# ST-Link-V2_2.net
KiCad netlist of a schematic drawn in Altium Designer
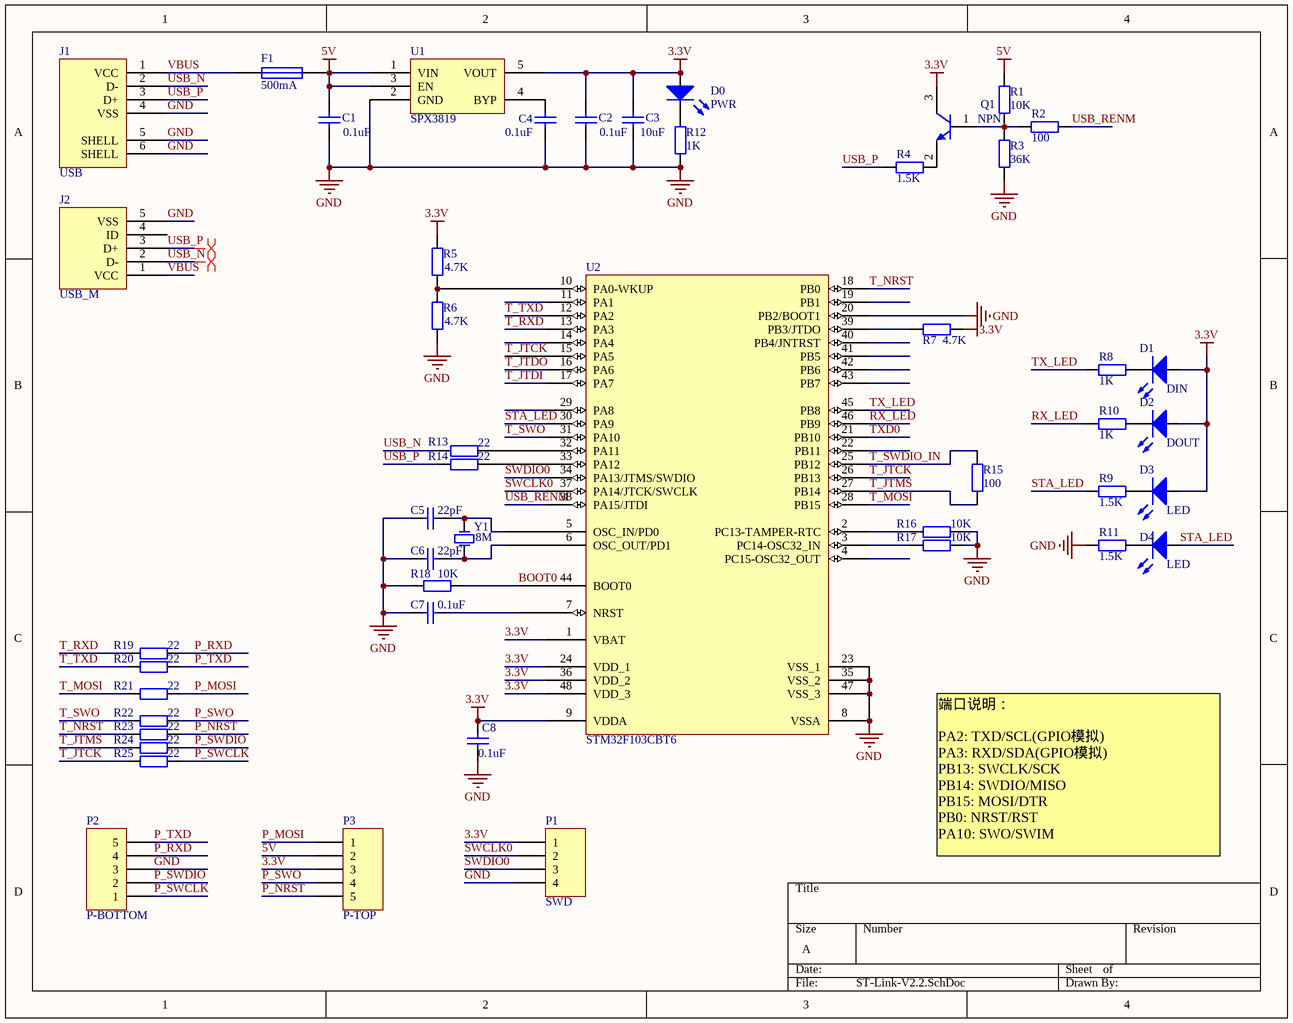
[diagram p0: ST-Link-V2.2.SchDoc]

(export (version "E")
  (design (tool "Eeschema 10.0.6"))
  (components
    (comp (ref "C1")
      (value "0.1uF")
      (footprint "C-0603")
      (description "Capacitor")
      (fields (field (name "Comment") "Cap") (field (name "PUBLISHER") "Altium Limited"))
      (libsource (lib "Miscellaneous Devices") (part "Cap"))
    )
    (comp (ref "C2")
      (value "0.1uF")
      (footprint "C-0603")
      (description "Capacitor")
      (fields (field (name "Comment") "Cap") (field (name "PUBLISHER") "Altium Limited"))
      (libsource (lib "Miscellaneous Devices") (part "Cap"))
    )
    (comp (ref "C3")
      (value "10uF")
      (footprint "C-0603")
      (description "Capacitor")
      (fields (field (name "Comment") "Cap") (field (name "PUBLISHER") "Altium Limited"))
      (libsource (lib "Miscellaneous Devices") (part "Cap"))
    )
    (comp (ref "C4")
      (value "0.1uF")
      (footprint "C-0603")
      (description "Capacitor")
      (fields (field (name "Comment") "Cap") (field (name "PUBLISHER") "Altium Limited"))
      (libsource (lib "Miscellaneous Devices") (part "Cap"))
    )
    (comp (ref "C5")
      (value "22pF")
      (footprint "C-0603")
      (fields (field (name "Comment") "Cap"))
      (libsource (lib "WK_PCB") (part "Cap"))
    )
    (comp (ref "C6")
      (value "22pF")
      (footprint "C-0603")
      (fields (field (name "Comment") "Cap"))
      (libsource (lib "WK_PCB") (part "Cap"))
    )
    (comp (ref "C7")
      (value "0.1uF")
      (footprint "C-0603")
      (fields (field (name "Comment") "Cap"))
      (libsource (lib "WK_PCB") (part "Cap"))
    )
    (comp (ref "C8")
      (value "0.1uF")
      (footprint "C-0603")
      (description "Capacitor")
      (fields (field (name "Comment") "Cap") (field (name "PUBLISHER") "Altium Limited"))
      (libsource (lib "Miscellaneous Devices") (part "Cap"))
    )
    (comp (ref "D0")
      (value "PWR")
      (footprint "SMT_LED_0603")
      (description "Typical RED, GREEN, YELLOW, AMBER GaAs LED")
      (fields (field (name "PUBLISHER") "Altium Limited"))
      (libsource (lib "ST-Link-V2.2") (part "LED2"))
    )
    (comp (ref "D1")
      (value "DIN")
      (footprint "SMT_LED_0603")
      (description "Typical RED, GREEN, YELLOW, AMBER GaAs LED")
      (fields (field (name "PUBLISHER") "Altium Limited"))
      (libsource (lib "ST-Link-V2.2") (part "LED2"))
    )
    (comp (ref "D2")
      (value "DOUT")
      (footprint "SMT_LED_0603")
      (description "Typical RED, GREEN, YELLOW, AMBER GaAs LED")
      (fields (field (name "PUBLISHER") "Altium Limited"))
      (libsource (lib "ST-Link-V2.2") (part "LED2"))
    )
    (comp (ref "D3")
      (value "LED")
      (footprint "SMT_LED_0603")
      (description "Typical RED, GREEN, YELLOW, AMBER GaAs LED")
      (fields (field (name "PUBLISHER") "Altium Limited"))
      (libsource (lib "ST-Link-V2.2") (part "LED2"))
    )
    (comp (ref "D4")
      (value "LED")
      (footprint "SMT_LED_0603")
      (description "Typical RED, GREEN, YELLOW, AMBER GaAs LED")
      (fields (field (name "PUBLISHER") "Altium Limited"))
      (libsource (lib "ST-Link-V2.2") (part "LED2"))
    )
    (comp (ref "F1")
      (value "500mA")
      (footprint "0805-1")
      (description "保险丝")
      (fields (field (name "Comment") "Fuse1"))
      (libsource (lib "ST-Link-V2.2") (part "Fuse1"))
    )
    (comp (ref "J1")
      (value "USB")
      (footprint "USB-B")
      (description "USB接口")
      (libsource (lib "HDR_Fszhang") (part "USB"))
    )
    (comp (ref "J2")
      (value "USB_M")
      (footprint "USB_MICRO_5S_B")
      (description "Micro/Mini USB")
      (libsource (lib "HDR_Fszhang") (part "USB_M"))
    )
    (comp (ref "P1")
      (value "SWD")
      (footprint "SIP4-1.27")
      (description "Header, 4-Pin")
      (fields (field (name "PUBLISHER") "Altium Limited"))
      (libsource (lib "Miscellaneous Connectors") (part "Header 4"))
    )
    (comp (ref "P2")
      (value "P-BOTTOM")
      (footprint "HEADER_5")
      (description "Header, 5-Pin")
      (fields (field (name "PUBLISHER") "Altium Limited"))
      (libsource (lib "") (part "Header 5_1"))
    )
    (comp (ref "P3")
      (value "P-TOP")
      (footprint "HEADER_5")
      (description "Header, 5-Pin")
      (fields (field (name "PUBLISHER") "Altium Limited"))
      (libsource (lib "Miscellaneous Connectors") (part "Header 5"))
    )
    (comp (ref "Q1")
      (value "NPN")
      (footprint "SOT23-3")
      (description "贴片三极管")
      (fields (field (name "PUBLISHER") "Altium Limited"))
      (libsource (lib "Fszhang") (part "NPN1"))
    )
    (comp (ref "R1")
      (value "10K")
      (footprint "0603-1")
      (description "贴片电阻")
      (fields (field (name "Comment") "Res1") (field (name "PUBLISHER") "Altium Limited"))
      (libsource (lib "Fszhang") (part "Res1"))
    )
    (comp (ref "R2")
      (value "100")
      (footprint "0603-1")
      (description "贴片电阻")
      (fields (field (name "Comment") "Res1") (field (name "PUBLISHER") "Altium Limited"))
      (libsource (lib "") (part "Res1_1"))
    )
    (comp (ref "R3")
      (value "36K")
      (footprint "0603-1")
      (description "贴片电阻")
      (fields (field (name "Comment") "Res1") (field (name "PUBLISHER") "Altium Limited"))
      (libsource (lib "Fszhang") (part "Res1"))
    )
    (comp (ref "R4")
      (value "1.5K")
      (footprint "0603-1")
      (description "贴片电阻")
      (fields (field (name "Comment") "Res1") (field (name "PUBLISHER") "Altium Limited"))
      (libsource (lib "") (part "Res1_2"))
    )
    (comp (ref "R5")
      (value "4.7K")
      (footprint "0603-1")
      (description "Resistor")
      (fields (field (name "Comment") "Res2") (field (name "PUBLISHER") "Altium Limited"))
      (libsource (lib "") (part "Res2_1"))
    )
    (comp (ref "R6")
      (value "4.7K")
      (footprint "0603-1")
      (description "Resistor")
      (fields (field (name "Comment") "Res2") (field (name "PUBLISHER") "Altium Limited"))
      (libsource (lib "") (part "Res2_1"))
    )
    (comp (ref "R7")
      (value "4.7K")
      (footprint "0603-1")
      (description "Resistor")
      (fields (field (name "Comment") "Res2") (field (name "PUBLISHER") "Altium Limited"))
      (libsource (lib "Miscellaneous Devices") (part "Res2"))
    )
    (comp (ref "R8")
      (value "1K")
      (footprint "0603-1")
      (description "Resistor")
      (fields (field (name "Comment") "Res2") (field (name "PUBLISHER") "Altium Limited"))
      (libsource (lib "Miscellaneous Devices") (part "Res2"))
    )
    (comp (ref "R9")
      (value "1.5K")
      (footprint "0603-1")
      (description "Resistor")
      (fields (field (name "Comment") "Res2") (field (name "PUBLISHER") "Altium Limited"))
      (libsource (lib "") (part "Res2_2"))
    )
    (comp (ref "R10")
      (value "1K")
      (footprint "0603-1")
      (description "Resistor")
      (fields (field (name "Comment") "Res2") (field (name "PUBLISHER") "Altium Limited"))
      (libsource (lib "Miscellaneous Devices") (part "Res2"))
    )
    (comp (ref "R11")
      (value "1.5K")
      (footprint "0603-1")
      (description "Resistor")
      (fields (field (name "Comment") "Res2") (field (name "PUBLISHER") "Altium Limited"))
      (libsource (lib "") (part "Res2_1"))
    )
    (comp (ref "R12")
      (value "1K")
      (footprint "0603-1")
      (description "Resistor")
      (fields (field (name "Comment") "Res2") (field (name "PUBLISHER") "Altium Limited"))
      (libsource (lib "") (part "Res2_1"))
    )
    (comp (ref "R13")
      (value "22")
      (footprint "0603-1")
      (description "Resistor")
      (fields (field (name "Comment") "Res2") (field (name "PUBLISHER") "Altium Limited"))
      (libsource (lib "Miscellaneous Devices") (part "Res2"))
    )
    (comp (ref "R14")
      (value "22")
      (footprint "0603-1")
      (description "Resistor")
      (fields (field (name "Comment") "Res2") (field (name "PUBLISHER") "Altium Limited"))
      (libsource (lib "Miscellaneous Devices") (part "Res2"))
    )
    (comp (ref "R15")
      (value "100")
      (footprint "0603-1")
      (description "Resistor")
      (fields (field (name "Comment") "Res2") (field (name "PUBLISHER") "Altium Limited"))
      (libsource (lib "") (part "Res2_1"))
    )
    (comp (ref "R16")
      (value "10K")
      (footprint "0603-1")
      (description "贴片电阻")
      (fields (field (name "Comment") "Res1") (field (name "PUBLISHER") "Altium Limited"))
      (libsource (lib "") (part "Res1_1"))
    )
    (comp (ref "R17")
      (value "10K")
      (footprint "0603-1")
      (description "贴片电阻")
      (fields (field (name "Comment") "Res1") (field (name "PUBLISHER") "Altium Limited"))
      (libsource (lib "") (part "Res1_1"))
    )
    (comp (ref "R18")
      (value "10K")
      (footprint "0603-1")
      (description "Resistor")
      (fields (field (name "Comment") "Res2") (field (name "PUBLISHER") "Altium Limited"))
      (libsource (lib "Miscellaneous Devices") (part "Res2"))
    )
    (comp (ref "R19")
      (value "22")
      (footprint "0603-1")
      (description "Resistor")
      (fields (field (name "Comment") "Res2") (field (name "PUBLISHER") "Altium Limited"))
      (libsource (lib "Miscellaneous Devices") (part "Res2"))
    )
    (comp (ref "R20")
      (value "22")
      (footprint "0603-1")
      (description "Resistor")
      (fields (field (name "Comment") "Res2") (field (name "PUBLISHER") "Altium Limited"))
      (libsource (lib "Miscellaneous Devices") (part "Res2"))
    )
    (comp (ref "R21")
      (value "22")
      (footprint "0603-1")
      (description "Resistor")
      (fields (field (name "Comment") "Res2") (field (name "PUBLISHER") "Altium Limited"))
      (libsource (lib "Miscellaneous Devices") (part "Res2"))
    )
    (comp (ref "R22")
      (value "22")
      (footprint "0603-1")
      (description "Resistor")
      (fields (field (name "Comment") "Res2") (field (name "PUBLISHER") "Altium Limited"))
      (libsource (lib "Miscellaneous Devices") (part "Res2"))
    )
    (comp (ref "R23")
      (value "22")
      (footprint "0603-1")
      (description "Resistor")
      (fields (field (name "Comment") "Res2") (field (name "PUBLISHER") "Altium Limited"))
      (libsource (lib "Miscellaneous Devices") (part "Res2"))
    )
    (comp (ref "R24")
      (value "22")
      (footprint "0603-1")
      (description "Resistor")
      (fields (field (name "Comment") "Res2") (field (name "PUBLISHER") "Altium Limited"))
      (libsource (lib "Miscellaneous Devices") (part "Res2"))
    )
    (comp (ref "R25")
      (value "22")
      (footprint "0603-1")
      (description "Resistor")
      (fields (field (name "Comment") "Res2") (field (name "PUBLISHER") "Altium Limited"))
      (libsource (lib "Miscellaneous Devices") (part "Res2"))
    )
    (comp (ref "U1") (value "SPX3819") (footprint "SOT23-5") (libsource (lib "Schlib1") (part "SPX3819")))
    (comp (ref "U2")
      (value "STM32F103CBT6")
      (footprint "LQFP48_N")
      (description "STM32 ARM-based 32-bit MCU with 64 Kbytes Flash, 48-pin LQFP, Industrial Temperature")
      (fields (field (name "PUBLISHER") "Altium Limited"))
      (libsource (lib "ST Microcontroller 32-Bit STM32") (part "STM32F103C8T6"))
    )
    (comp (ref "Y1")
      (value "8M")
      (footprint "XAL5032 2-Leads")
      (description "Crystal Oscillator")
      (fields
        (field (name "MANUFACTURER") "Generic Components")
        (field (name "PUBLISHER") "Altium Hobart Technology Centre")
      )
      (libsource (lib "*") (part "XTAL"))
    )
  )
  (nets
    (net (code "1") (name "/BOOT0") (class "Default")
      (node (ref "R18") (pin "2") (pinfunction "2_2") (pintype "passive"))
      (node (ref "U2") (pin "44") (pinfunction "BOOT0_44") (pintype "passive"))
    )
    (net (code "2") (name "/P_MOSI") (class "Default")
      (node (ref "P3") (pin "1") (pinfunction "1_1") (pintype "passive"))
      (node (ref "R21") (pin "2") (pinfunction "2_2") (pintype "passive"))
    )
    (net (code "3") (name "/P_NRST") (class "Default")
      (node (ref "P3") (pin "5") (pinfunction "5_5") (pintype "passive"))
      (node (ref "R23") (pin "2") (pinfunction "2_2") (pintype "passive"))
    )
    (net (code "4") (name "/P_RXD") (class "Default")
      (node (ref "P2") (pin "4") (pinfunction "4_4") (pintype "passive"))
      (node (ref "R19") (pin "2") (pinfunction "2_2") (pintype "passive"))
    )
    (net (code "5") (name "/P_SWCLK") (class "Default")
      (node (ref "P2") (pin "1") (pinfunction "1_1") (pintype "passive"))
      (node (ref "R25") (pin "2") (pinfunction "2_2") (pintype "passive"))
    )
    (net (code "6") (name "/P_SWDIO") (class "Default")
      (node (ref "P2") (pin "2") (pinfunction "2_2") (pintype "passive"))
      (node (ref "R24") (pin "2") (pinfunction "2_2") (pintype "passive"))
    )
    (net (code "7") (name "/P_SWO") (class "Default")
      (node (ref "P3") (pin "4") (pinfunction "4_4") (pintype "passive"))
      (node (ref "R22") (pin "2") (pinfunction "2_2") (pintype "passive"))
    )
    (net (code "8") (name "/P_TXD") (class "Default")
      (node (ref "P2") (pin "5") (pinfunction "5_5") (pintype "passive"))
      (node (ref "R20") (pin "2") (pinfunction "2_2") (pintype "passive"))
    )
    (net (code "9") (name "/RX_LED") (class "Default")
      (node (ref "R10") (pin "1") (pinfunction "1_1") (pintype "passive"))
      (node (ref "U2") (pin "46") (pinfunction "PB9_46") (pintype "bidirectional"))
    )
    (net (code "10") (name "/STA_LED") (class "Default")
      (node (ref "D4") (pin "1") (pinfunction "A_1") (pintype "passive"))
      (node (ref "R9") (pin "2") (pinfunction "2_2") (pintype "passive"))
      (node (ref "U2") (pin "30") (pinfunction "PA9_30") (pintype "bidirectional"))
    )
    (net (code "11") (name "/SWCLK0") (class "Default")
      (node (ref "P1") (pin "2") (pinfunction "2_2") (pintype "passive"))
      (node (ref "U2") (pin "37") (pinfunction "PA14/JTCK/SWCLK_37") (pintype "bidirectional"))
    )
    (net (code "12") (name "/SWDIO0") (class "Default")
      (node (ref "P1") (pin "3") (pinfunction "3_3") (pintype "passive"))
      (node (ref "U2") (pin "34") (pinfunction "PA13/JTMS/SWDIO_34") (pintype "bidirectional"))
    )
    (net (code "13") (name "/TXD0") (class "Default")
      (node (ref "U2") (pin "21") (pinfunction "PB10_21") (pintype "bidirectional"))
    )
    (net (code "14") (name "/TX_LED") (class "Default")
      (node (ref "R8") (pin "1") (pinfunction "1_1") (pintype "passive"))
      (node (ref "U2") (pin "45") (pinfunction "PB8_45") (pintype "bidirectional"))
    )
    (net (code "15") (name "/T_JTCK") (class "Default")
      (node (ref "R25") (pin "1") (pinfunction "1_1") (pintype "passive"))
      (node (ref "U2") (pin "15") (pinfunction "PA5_15") (pintype "bidirectional"))
      (node (ref "U2") (pin "26") (pinfunction "PB13_26") (pintype "bidirectional"))
    )
    (net (code "16") (name "/T_JTDI") (class "Default")
      (node (ref "U2") (pin "17") (pinfunction "PA7_17") (pintype "bidirectional"))
    )
    (net (code "17") (name "/T_JTDO") (class "Default")
      (node (ref "U2") (pin "16") (pinfunction "PA6_16") (pintype "bidirectional"))
    )
    (net (code "18") (name "/T_JTMS") (class "Default")
      (node (ref "R15") (pin "1") (pinfunction "1_1") (pintype "passive"))
      (node (ref "R24") (pin "1") (pinfunction "1_1") (pintype "passive"))
      (node (ref "U2") (pin "27") (pinfunction "PB14_27") (pintype "bidirectional"))
    )
    (net (code "19") (name "/T_MOSI") (class "Default")
      (node (ref "R21") (pin "1") (pinfunction "1_1") (pintype "passive"))
      (node (ref "U2") (pin "28") (pinfunction "PB15_28") (pintype "bidirectional"))
    )
    (net (code "20") (name "/T_NRST") (class "Default")
      (node (ref "R23") (pin "1") (pinfunction "1_1") (pintype "passive"))
      (node (ref "U2") (pin "18") (pinfunction "PB0_18") (pintype "bidirectional"))
    )
    (net (code "21") (name "/T_RXD") (class "Default")
      (node (ref "R19") (pin "1") (pinfunction "1_1") (pintype "passive"))
      (node (ref "U2") (pin "13") (pinfunction "PA3_13") (pintype "bidirectional"))
    )
    (net (code "22") (name "/T_SWDIO_IN") (class "Default")
      (node (ref "R15") (pin "2") (pinfunction "2_2") (pintype "passive"))
      (node (ref "U2") (pin "25") (pinfunction "PB12_25") (pintype "bidirectional"))
    )
    (net (code "23") (name "/T_SWO") (class "Default")
      (node (ref "R22") (pin "1") (pinfunction "1_1") (pintype "passive"))
      (node (ref "U2") (pin "31") (pinfunction "PA10_31") (pintype "bidirectional"))
    )
    (net (code "24") (name "/T_TXD") (class "Default")
      (node (ref "R20") (pin "1") (pinfunction "1_1") (pintype "passive"))
      (node (ref "U2") (pin "12") (pinfunction "PA2_12") (pintype "bidirectional"))
    )
    (net (code "25") (name "/USB_N") (class "Default")
      (node (ref "J1") (pin "2") (pinfunction "D-_2") (pintype "passive"))
      (node (ref "J2") (pin "2") (pinfunction "D-_2") (pintype "passive"))
      (node (ref "R13") (pin "1") (pinfunction "1_1") (pintype "passive"))
    )
    (net (code "26") (name "/USB_P") (class "Default")
      (node (ref "J1") (pin "3") (pinfunction "D+_3") (pintype "passive"))
      (node (ref "J2") (pin "3") (pinfunction "D+_3") (pintype "passive"))
      (node (ref "R14") (pin "1") (pinfunction "1_1") (pintype "passive"))
      (node (ref "R4") (pin "2") (pinfunction "2_2") (pintype "passive"))
    )
    (net (code "27") (name "/USB_RENM") (class "Default")
      (node (ref "R2") (pin "2") (pinfunction "2_2") (pintype "passive"))
      (node (ref "U2") (pin "38") (pinfunction "PA15/JTDI_38") (pintype "bidirectional"))
    )
    (net (code "28") (name "/VBUS") (class "Default")
      (node (ref "F1") (pin "1") (pinfunction "1_1") (pintype "passive"))
      (node (ref "J1") (pin "1") (pinfunction "VCC_1") (pintype "passive"))
      (node (ref "J2") (pin "1") (pinfunction "VCC_1") (pintype "passive"))
    )
    (net (code "29") (name "3.3V") (class "Default")
      (node (ref "C2") (pin "2") (pinfunction "2_2") (pintype "passive"))
      (node (ref "C3") (pin "2") (pinfunction "2_2") (pintype "passive"))
      (node (ref "C8") (pin "2") (pinfunction "2_2") (pintype "passive"))
      (node (ref "D0") (pin "1") (pinfunction "A_1") (pintype "passive"))
      (node (ref "D1") (pin "1") (pinfunction "A_1") (pintype "passive"))
      (node (ref "D2") (pin "1") (pinfunction "A_1") (pintype "passive"))
      (node (ref "D3") (pin "1") (pinfunction "A_1") (pintype "passive"))
      (node (ref "P1") (pin "1") (pinfunction "1_1") (pintype "passive"))
      (node (ref "P3") (pin "3") (pinfunction "3_3") (pintype "passive"))
      (node (ref "Q1") (pin "3") (pinfunction "C_3") (pintype "passive"))
      (node (ref "R5") (pin "2") (pinfunction "2_2") (pintype "passive"))
      (node (ref "R7") (pin "2") (pinfunction "2_2") (pintype "passive"))
      (node (ref "U1") (pin "5") (pinfunction "VOUT_5") (pintype "passive"))
      (node (ref "U2") (pin "1") (pinfunction "VBAT_1") (pintype "power_in"))
      (node (ref "U2") (pin "24") (pinfunction "VDD_1_24") (pintype "power_in"))
      (node (ref "U2") (pin "36") (pinfunction "VDD_2_36") (pintype "power_in"))
      (node (ref "U2") (pin "48") (pinfunction "VDD_3_48") (pintype "power_in"))
      (node (ref "U2") (pin "9") (pinfunction "VDDA_9") (pintype "power_in"))
    )
    (net (code "30") (name "5V") (class "Default")
      (node (ref "C1") (pin "2") (pinfunction "2_2") (pintype "passive"))
      (node (ref "F1") (pin "2") (pinfunction "2_2") (pintype "passive"))
      (node (ref "P3") (pin "2") (pinfunction "2_2") (pintype "passive"))
      (node (ref "R1") (pin "1") (pinfunction "1_1") (pintype "passive"))
      (node (ref "U1") (pin "1") (pinfunction "VIN_1") (pintype "passive"))
      (node (ref "U1") (pin "3") (pinfunction "EN_3") (pintype "passive"))
    )
    (net (code "31") (name "GND") (class "Default")
      (node (ref "C1") (pin "1") (pinfunction "1_1") (pintype "passive"))
      (node (ref "C2") (pin "1") (pinfunction "1_1") (pintype "passive"))
      (node (ref "C3") (pin "1") (pinfunction "1_1") (pintype "passive"))
      (node (ref "C4") (pin "1") (pinfunction "1_1") (pintype "passive"))
      (node (ref "C5") (pin "1") (pinfunction "1_1") (pintype "passive"))
      (node (ref "C6") (pin "1") (pinfunction "1_1") (pintype "passive"))
      (node (ref "C7") (pin "1") (pinfunction "1_1") (pintype "passive"))
      (node (ref "C8") (pin "1") (pinfunction "1_1") (pintype "passive"))
      (node (ref "J1") (pin "4") (pinfunction "VSS_4") (pintype "passive"))
      (node (ref "J1") (pin "5") (pinfunction "SHELL_5") (pintype "passive"))
      (node (ref "J1") (pin "6") (pinfunction "SHELL_6") (pintype "passive"))
      (node (ref "J2") (pin "5") (pinfunction "VSS_5") (pintype "passive"))
      (node (ref "P1") (pin "4") (pinfunction "4_4") (pintype "passive"))
      (node (ref "P2") (pin "3") (pinfunction "3_3") (pintype "passive"))
      (node (ref "R11") (pin "1") (pinfunction "1_1") (pintype "passive"))
      (node (ref "R12") (pin "1") (pinfunction "1_1") (pintype "passive"))
      (node (ref "R16") (pin "2") (pinfunction "2_2") (pintype "passive"))
      (node (ref "R17") (pin "2") (pinfunction "2_2") (pintype "passive"))
      (node (ref "R18") (pin "1") (pinfunction "1_1") (pintype "passive"))
      (node (ref "R3") (pin "2") (pinfunction "2_2") (pintype "passive"))
      (node (ref "R6") (pin "1") (pinfunction "1_1") (pintype "passive"))
      (node (ref "U1") (pin "2") (pinfunction "GND_2") (pintype "passive"))
      (node (ref "U2") (pin "20") (pinfunction "PB2/BOOT1_20") (pintype "bidirectional"))
      (node (ref "U2") (pin "23") (pinfunction "VSS_1_23") (pintype "power_in"))
      (node (ref "U2") (pin "35") (pinfunction "VSS_2_35") (pintype "power_in"))
      (node (ref "U2") (pin "47") (pinfunction "VSS_3_47") (pintype "power_in"))
      (node (ref "U2") (pin "8") (pinfunction "VSSA_8") (pintype "power_in"))
    )
    (net (code "32") (name "Net-(D0-K)") (class "Default")
      (node (ref "D0") (pin "2") (pinfunction "K_2") (pintype "passive"))
      (node (ref "R12") (pin "2") (pinfunction "2_2") (pintype "passive"))
    )
    (net (code "33") (name "Net-(D1-K)") (class "Default")
      (node (ref "D1") (pin "2") (pinfunction "K_2") (pintype "passive"))
      (node (ref "R8") (pin "2") (pinfunction "2_2") (pintype "passive"))
    )
    (net (code "34") (name "Net-(D2-K)") (class "Default")
      (node (ref "D2") (pin "2") (pinfunction "K_2") (pintype "passive"))
      (node (ref "R10") (pin "2") (pinfunction "2_2") (pintype "passive"))
    )
    (net (code "35") (name "Net-(D3-K)") (class "Default")
      (node (ref "D3") (pin "2") (pinfunction "K_2") (pintype "passive"))
      (node (ref "R9") (pin "1") (pinfunction "1_1") (pintype "passive"))
    )
    (net (code "36") (name "Net-(D4-K)") (class "Default")
      (node (ref "D4") (pin "2") (pinfunction "K_2") (pintype "passive"))
      (node (ref "R11") (pin "2") (pinfunction "2_2") (pintype "passive"))
    )
    (net (code "37") (name "Net-(Q1-B)") (class "Default")
      (node (ref "Q1") (pin "1") (pinfunction "B_1") (pintype "passive"))
      (node (ref "R1") (pin "2") (pinfunction "2_2") (pintype "passive"))
      (node (ref "R2") (pin "1") (pinfunction "1_1") (pintype "passive"))
      (node (ref "R3") (pin "1") (pinfunction "1_1") (pintype "passive"))
    )
    (net (code "38") (name "Net-(Q1-E)") (class "Default")
      (node (ref "Q1") (pin "2") (pinfunction "E_2") (pintype "passive"))
      (node (ref "R4") (pin "1") (pinfunction "1_1") (pintype "passive"))
    )
    (net (code "39") (name "Net-(U1-BYP)") (class "Default")
      (node (ref "C4") (pin "2") (pinfunction "2_2") (pintype "passive"))
      (node (ref "U1") (pin "4") (pinfunction "BYP_4") (pintype "passive"))
    )
    (net (code "40") (name "Net-(U2-NRST)") (class "Default")
      (node (ref "C7") (pin "2") (pinfunction "2_2") (pintype "passive"))
      (node (ref "U2") (pin "7") (pinfunction "NRST_7") (pintype "bidirectional"))
    )
    (net (code "41") (name "Net-(U2-OSC_IN{slash}PD0)") (class "Default")
      (node (ref "C5") (pin "2") (pinfunction "2_2") (pintype "passive"))
      (node (ref "U2") (pin "5") (pinfunction "OSC_IN/PD0_5") (pintype "passive"))
      (node (ref "Y1") (pin "1") (pinfunction "OSC1_1") (pintype "passive"))
    )
    (net (code "42") (name "Net-(U2-OSC_OUT{slash}PD1)") (class "Default")
      (node (ref "C6") (pin "2") (pinfunction "2_2") (pintype "passive"))
      (node (ref "U2") (pin "6") (pinfunction "OSC_OUT/PD1_6") (pintype "passive"))
      (node (ref "Y1") (pin "2") (pinfunction "OSC2_2") (pintype "passive"))
    )
    (net (code "43") (name "Net-(U2-PA0-WKUP)") (class "Default")
      (node (ref "R5") (pin "1") (pinfunction "1_1") (pintype "passive"))
      (node (ref "R6") (pin "2") (pinfunction "2_2") (pintype "passive"))
      (node (ref "U2") (pin "10") (pinfunction "PA0-WKUP_10") (pintype "bidirectional"))
    )
    (net (code "44") (name "Net-(U2-PA11)") (class "Default")
      (node (ref "R13") (pin "2") (pinfunction "2_2") (pintype "passive"))
      (node (ref "U2") (pin "32") (pinfunction "PA11_32") (pintype "bidirectional"))
    )
    (net (code "45") (name "Net-(U2-PA12)") (class "Default")
      (node (ref "R14") (pin "2") (pinfunction "2_2") (pintype "passive"))
      (node (ref "U2") (pin "33") (pinfunction "PA12_33") (pintype "bidirectional"))
    )
    (net (code "46") (name "Net-(U2-PB3{slash}JTDO)") (class "Default")
      (node (ref "R7") (pin "1") (pinfunction "1_1") (pintype "passive"))
      (node (ref "U2") (pin "39") (pinfunction "PB3/JTDO_39") (pintype "bidirectional"))
    )
    (net (code "47") (name "Net-(U2-PC13-TAMPER-RTC)") (class "Default")
      (node (ref "R16") (pin "1") (pinfunction "1_1") (pintype "passive"))
      (node (ref "U2") (pin "2") (pinfunction "PC13-TAMPER-RTC_2") (pintype "bidirectional"))
    )
    (net (code "48") (name "Net-(U2-PC14-OSC32_IN)") (class "Default")
      (node (ref "R17") (pin "1") (pinfunction "1_1") (pintype "passive"))
      (node (ref "U2") (pin "3") (pinfunction "PC14-OSC32_IN_3") (pintype "bidirectional"))
    )
    (net (code "49") (name "unconnected-(J2-ID-Pad4)") (class "Default")
      (node (ref "J2") (pin "4") (pinfunction "ID_4") (pintype "passive"))
    )
    (net (code "50") (name "unconnected-(U2-PA1-Pad11)") (class "Default")
      (node (ref "U2") (pin "11") (pinfunction "PA1_11") (pintype "bidirectional"))
    )
    (net (code "51") (name "unconnected-(U2-PA4-Pad14)") (class "Default")
      (node (ref "U2") (pin "14") (pinfunction "PA4_14") (pintype "bidirectional"))
    )
    (net (code "52") (name "unconnected-(U2-PA8-Pad29)") (class "Default")
      (node (ref "U2") (pin "29") (pinfunction "PA8_29") (pintype "bidirectional"))
    )
    (net (code "53") (name "unconnected-(U2-PB1-Pad19)") (class "Default")
      (node (ref "U2") (pin "19") (pinfunction "PB1_19") (pintype "bidirectional"))
    )
    (net (code "54") (name "unconnected-(U2-PB4{slash}JNTRST-Pad40)") (class "Default")
      (node (ref "U2") (pin "40") (pinfunction "PB4/JNTRST_40") (pintype "bidirectional"))
    )
    (net (code "55") (name "unconnected-(U2-PB5-Pad41)") (class "Default")
      (node (ref "U2") (pin "41") (pinfunction "PB5_41") (pintype "bidirectional"))
    )
    (net (code "56") (name "unconnected-(U2-PB6-Pad42)") (class "Default")
      (node (ref "U2") (pin "42") (pinfunction "PB6_42") (pintype "bidirectional"))
    )
    (net (code "57") (name "unconnected-(U2-PB7-Pad43)") (class "Default")
      (node (ref "U2") (pin "43") (pinfunction "PB7_43") (pintype "bidirectional"))
    )
    (net (code "58") (name "unconnected-(U2-PB11-Pad22)") (class "Default")
      (node (ref "U2") (pin "22") (pinfunction "PB11_22") (pintype "bidirectional"))
    )
    (net (code "59") (name "unconnected-(U2-PC15-OSC32_OUT-Pad4)") (class "Default")
      (node (ref "U2") (pin "4") (pinfunction "PC15-OSC32_OUT_4") (pintype "bidirectional"))
    )
  )
)
